# ADC_PLL.net
KiCad netlist of a schematic drawn in Altium Designer
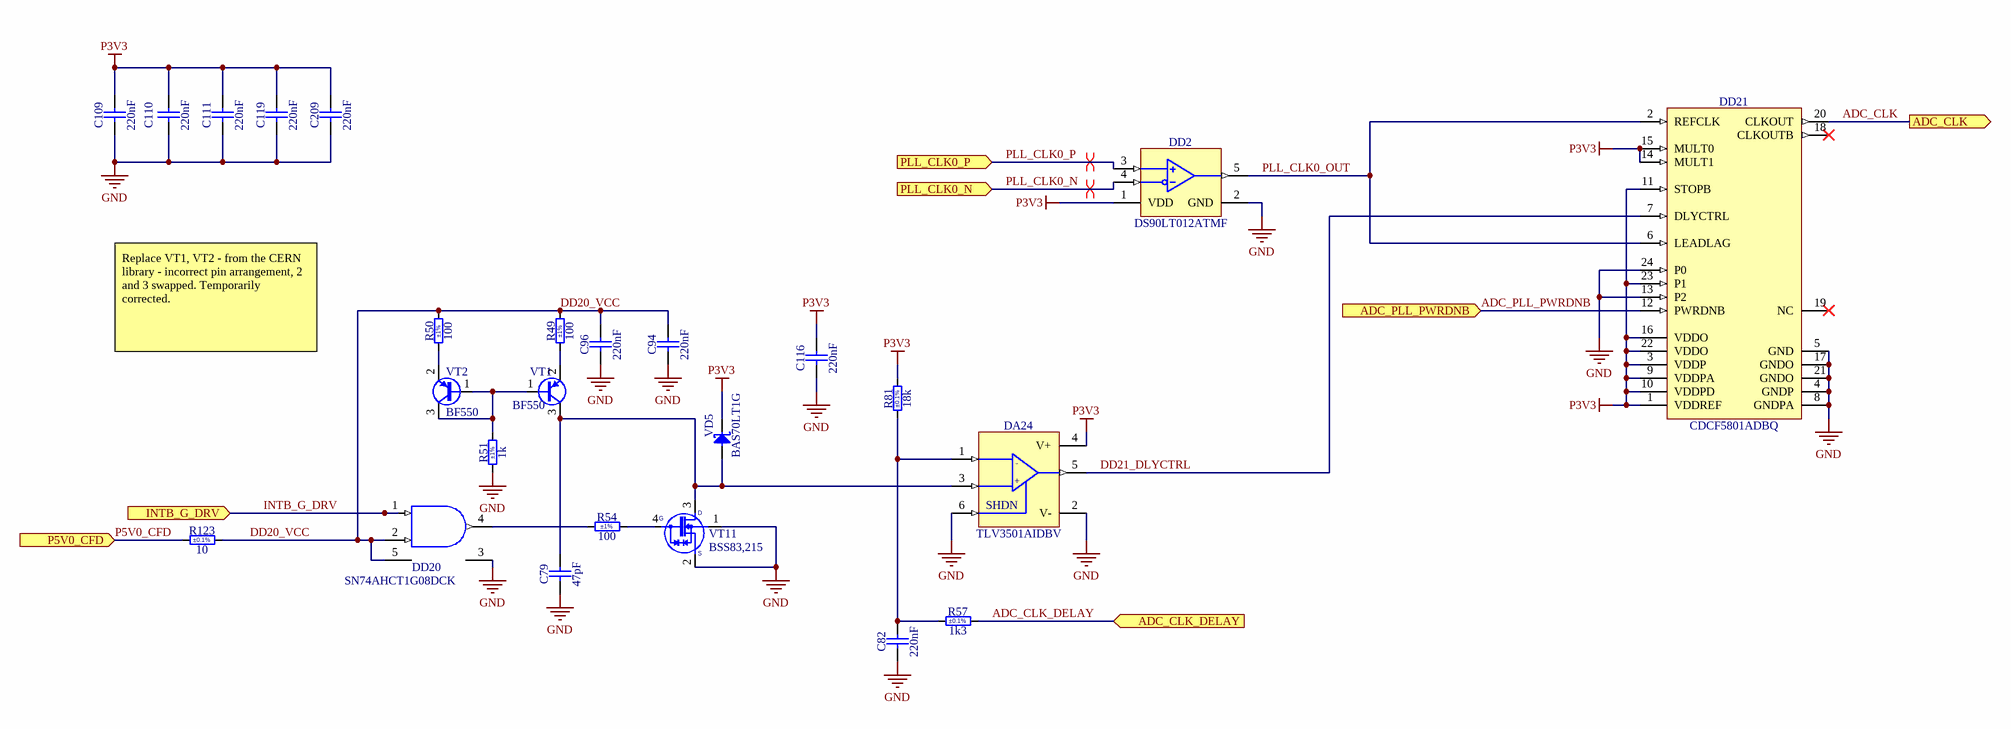
[diagram p0: ADC_PLL.SchDoc]

(export (version "E")
  (design (tool "Eeschema 10.0.6"))
  (components
    (comp (ref "C79")
      (value "47pF")
      (footprint "CAPC2012X140N")
      (description "Non-polarised capacitor")
      (fields
        (field (name "PART NUMBER") "CC0805_47pF_50V_2%_X8R")
        (field (name "VOLTAGE") "50V")
        (field (name "AUTHOR") "CERN DEM HF")
      )
      (libsource (lib "Capacitors") (part "Capacitor - non polarized"))
    )
    (comp (ref "C82")
      (value "220nF")
      (footprint "CAPC2012X135N")
      (description "Non-polarised capacitor")
      (fields
        (field (name "PART NUMBER") "CC0805_220NF_50V_10%_X7R")
        (field (name "VOLTAGE") "50V")
        (field (name "AUTHOR") "CERN DEM JLC")
      )
      (libsource (lib "Capacitors") (part "Capacitor - non polarized"))
    )
    (comp (ref "C94")
      (value "220nF")
      (footprint "CAPC2012X135N")
      (description "Non-polarised capacitor")
      (fields
        (field (name "PART NUMBER") "CC0805_220NF_50V_10%_X7R")
        (field (name "VOLTAGE") "50V")
        (field (name "AUTHOR") "CERN DEM JLC")
      )
      (libsource (lib "Capacitors") (part "Capacitor - non polarized"))
    )
    (comp (ref "C96")
      (value "220nF")
      (footprint "CAPC2012X135N")
      (description "Non-polarised capacitor")
      (fields
        (field (name "PART NUMBER") "CC0805_220NF_50V_10%_X7R")
        (field (name "VOLTAGE") "50V")
        (field (name "AUTHOR") "CERN DEM JLC")
      )
      (libsource (lib "Capacitors") (part "Capacitor - non polarized"))
    )
    (comp (ref "C109")
      (value "220nF")
      (footprint "CAPC2012X135N")
      (description "Non-polarised capacitor")
      (fields
        (field (name "PART NUMBER") "CC0805_220NF_50V_10%_X7R")
        (field (name "VOLTAGE") "50V")
        (field (name "AUTHOR") "CERN DEM JLC")
      )
      (libsource (lib "Capacitors") (part "Capacitor - non polarized"))
    )
    (comp (ref "C110")
      (value "220nF")
      (footprint "CAPC2012X135N")
      (description "Non-polarised capacitor")
      (fields
        (field (name "PART NUMBER") "CC0805_220NF_50V_10%_X7R")
        (field (name "VOLTAGE") "50V")
        (field (name "AUTHOR") "CERN DEM JLC")
      )
      (libsource (lib "Capacitors") (part "Capacitor - non polarized"))
    )
    (comp (ref "C111")
      (value "220nF")
      (footprint "CAPC2012X135N")
      (description "Non-polarised capacitor")
      (fields
        (field (name "PART NUMBER") "CC0805_220NF_50V_10%_X7R")
        (field (name "VOLTAGE") "50V")
        (field (name "AUTHOR") "CERN DEM JLC")
      )
      (libsource (lib "Capacitors") (part "Capacitor - non polarized"))
    )
    (comp (ref "C116")
      (value "220nF")
      (footprint "CAPC2012X135N")
      (description "Non-polarised capacitor")
      (fields
        (field (name "PART NUMBER") "CC0805_220NF_50V_10%_X7R")
        (field (name "VOLTAGE") "50V")
        (field (name "AUTHOR") "CERN DEM JLC")
      )
      (libsource (lib "Capacitors") (part "Capacitor - non polarized"))
    )
    (comp (ref "C119")
      (value "220nF")
      (footprint "CAPC2012X135N")
      (description "Non-polarised capacitor")
      (fields
        (field (name "PART NUMBER") "CC0805_220NF_50V_10%_X7R")
        (field (name "VOLTAGE") "50V")
        (field (name "AUTHOR") "CERN DEM JLC")
      )
      (libsource (lib "Capacitors") (part "Capacitor - non polarized"))
    )
    (comp (ref "C209")
      (value "220nF")
      (footprint "CAPC2012X135N")
      (description "Non-polarised capacitor")
      (fields
        (field (name "PART NUMBER") "CC0805_220NF_50V_10%_X7R")
        (field (name "VOLTAGE") "50V")
        (field (name "AUTHOR") "CERN DEM JLC")
      )
      (libsource (lib "Capacitors") (part "Capacitor - non polarized"))
    )
    (comp (ref "DA24")
      (value "TLV3501AIDBV")
      (footprint "SOT95P280X145-6N")
      (description "Wideband, Fixed Gain, Video Buffer Amplifier With Disable")
      (fields (field (name "MANUFACTURER") "TEXAS INSTRUMENTS") (field (name "AUTHOR") "CERN DEM HF"))
      (libsource (lib "ICs And Semiconductors") (part "TLV3501AIDBV"))
    )
    (comp (ref "DD2")
      (value "DS90LT012ATMF")
      (footprint "SOT95P280X145-5N")
      (description "3V LVDS Single CMOS Differential Line Receiver")
      (fields (field (name "MANUFACTURER") "TEXAS INSTRUMENTS") (field (name "AUTHOR") "CERN DEM HF"))
      (libsource (lib "ICs And Semiconductors") (part "DS90LT012A"))
    )
    (comp (ref "DD20")
      (value "SN74AHCT1G08DCK")
      (footprint "SOT65P210X110-5N")
      (description "Single 2-Input AND Gate")
      (fields (field (name "MANUFACTURER") "TEXAS INSTRUMENTS") (field (name "AUTHOR") "CERN DEM HF"))
      (libsource (lib "ICs And Semiconductors") (part "741G08"))
    )
    (comp (ref "DD21")
      (value "CDCF5801ADBQ")
      (footprint "SOP63P600X175-24N")
      (description "Clock Multiplier with Delay Control and Phase Alignment")
      (fields (field (name "MANUFACTURER") "TEXAS INSTRUMENTS") (field (name "AUTHOR") "CERN DEM HF"))
      (libsource (lib "ICs And Semiconductors") (part "CDCF5801ADBQ"))
    )
    (comp (ref "R49")
      (value "100")
      (footprint "RESC2012X60N")
      (description "Resistor - 1%")
      (fields
        (field (name "TOLERANCE") "±1%")
        (field (name "PART NUMBER") "R0805_100R_1%_0.125W_100PPM")
        (field (name "POWER") "0.125W")
        (field (name "AUTHOR") "CERN DEM JLC")
      )
      (libsource (lib "Resistors") (part "Resistor - 1%"))
    )
    (comp (ref "R50")
      (value "100")
      (footprint "RESC2012X60N")
      (description "Resistor - 1%")
      (fields
        (field (name "TOLERANCE") "±1%")
        (field (name "PART NUMBER") "R0805_100R_1%_0.125W_100PPM")
        (field (name "POWER") "0.125W")
        (field (name "AUTHOR") "CERN DEM JLC")
      )
      (libsource (lib "Resistors") (part "Resistor - 1%"))
    )
    (comp (ref "R51")
      (value "1k")
      (footprint "RESC2012X60N")
      (description "Resistor - 1%")
      (fields
        (field (name "TOLERANCE") "±1%")
        (field (name "PART NUMBER") "R0805_1K_1%_0.125W_100PPM")
        (field (name "POWER") "0.125W")
        (field (name "AUTHOR") "CERN DEM JLC")
      )
      (libsource (lib "Resistors") (part "Resistor - 1%"))
    )
    (comp (ref "R54")
      (value "100")
      (footprint "RESC1608X55N")
      (description "Resistor - 1%")
      (fields
        (field (name "TOLERANCE") "±1%")
        (field (name "PART NUMBER") "R0603_100R_1%_0.1W_100PPM")
        (field (name "POWER") "0.1W")
        (field (name "AUTHOR") "CERN DEM JLC")
      )
      (libsource (lib "Resistors") (part "Resistor - 1%"))
    )
    (comp (ref "R57")
      (value "1k3")
      (footprint "RESC2012X60N")
      (description "Resistor - 0.1%")
      (fields
        (field (name "TOLERANCE") "±0.1%")
        (field (name "PART NUMBER") "R0805_1K3_0.1%_0.1W_10PPM")
        (field (name "POWER") "0.1W")
        (field (name "AUTHOR") "CERN DEM JLC")
      )
      (libsource (lib "Resistors") (part "Resistor - 0.1%"))
    )
    (comp (ref "R81")
      (value "18k")
      (footprint "RESC2012X60N")
      (description "Resistor - 0.1%")
      (fields
        (field (name "TOLERANCE") "±0.1%")
        (field (name "PART NUMBER") "R0805_18K_0.1%_0.125W_10PPM")
        (field (name "POWER") "0.125W")
        (field (name "AUTHOR") "CERN DEM HF")
      )
      (libsource (lib "Resistors") (part "Resistor - 0.1%"))
    )
    (comp (ref "R123")
      (value "10")
      (footprint "RESC2012X60N")
      (description "Resistor - 0.1%")
      (fields
        (field (name "TOLERANCE") "±0.1%")
        (field (name "PART NUMBER") "R0805_10R_0.1%_0.1W_10PPM")
        (field (name "POWER") "0.1W")
        (field (name "AUTHOR") "CERN DEM JLC")
      )
      (libsource (lib "Resistors") (part "Resistor - 0.1%"))
    )
    (comp (ref "VD5")
      (value "BAS70LT1G")
      (footprint "SOT95P240X110-3N")
      (description "Diode Schottky  Anode Pin 1 Cathode Pin 3 (Pas de pin 2)")
      (fields
        (field (name "VOLTAGE") "70V")
        (field (name "POWER") "70mA")
        (field (name "AUTHOR") "CERN DEM JLC")
      )
      (libsource (lib "ICs And Semiconductors") (part "Diode Schottky A1C3"))
    )
    (comp (ref "VT1")
      (value "BF550")
      (footprint "SOT95P230X110-3N")
      (description "PNP Transistor")
      (fields (field (name "MANUFACTURER") "NXP SEMICONDUCTORS") (field (name "AUTHOR") "CERN DEM HF"))
      (libsource (lib "ICs And Semiconductors") (part "PNP B1 C2 E3"))
    )
    (comp (ref "VT2")
      (value "BF550")
      (footprint "SOT95P230X110-3N")
      (description "PNP Transistor")
      (fields (field (name "MANUFACTURER") "NXP SEMICONDUCTORS") (field (name "AUTHOR") "CERN DEM HF"))
      (libsource (lib "ICs And Semiconductors") (part "PNP B1 C2 E3"))
    )
    (comp (ref "VT11")
      (value "BSS83,215")
      (footprint "SOT143N")
      (description "10V, 50 mA N-Channel Enhancement Switching Transistor")
      (fields (field (name "MANUFACTURER") "NXP SEMICONDUCTORS") (field (name "AUTHOR") "CERN DEM JLC"))
      (libsource (lib "ICs And Semiconductors") (part "BSS83"))
    )
  )
  (nets
    (net (code "1") (name "/ADC_CLK") (class "Default")
      (node (ref "DD21") (pin "20") (pinfunction "CLKOUT_20") (pintype "output"))
    )
    (net (code "2") (name "/ADC_CLK_DELAY") (class "Default")
      (node (ref "R57") (pin "2") (pinfunction "2_2") (pintype "passive"))
    )
    (net (code "3") (name "/ADC_PLL_PWRDNB") (class "Default")
      (node (ref "DD21") (pin "12") (pinfunction "PWRDNB_12") (pintype "input"))
    )
    (net (code "4") (name "/DD20_VCC") (class "Default")
      (node (ref "C94") (pin "2") (pinfunction "2_2") (pintype "passive"))
      (node (ref "C96") (pin "2") (pinfunction "2_2") (pintype "passive"))
      (node (ref "DD20") (pin "2") (pinfunction "A_2") (pintype "input"))
      (node (ref "DD20") (pin "5") (pinfunction "VCC_5") (pintype "power_in"))
      (node (ref "R123") (pin "2") (pinfunction "2_2") (pintype "passive"))
      (node (ref "R49") (pin "2") (pinfunction "2_2") (pintype "passive"))
      (node (ref "R50") (pin "2") (pinfunction "2_2") (pintype "passive"))
    )
    (net (code "5") (name "/DD21_DLYCTRL") (class "Default")
      (node (ref "DA24") (pin "5") (pinfunction "OUT_5") (pintype "output"))
      (node (ref "DD21") (pin "7") (pinfunction "DLYCTRL_7") (pintype "input"))
    )
    (net (code "6") (name "/INTB_G_DRV") (class "Default")
      (node (ref "DD20") (pin "1") (pinfunction "B_1") (pintype "input"))
    )
    (net (code "7") (name "/P5V0_CFD") (class "Default")
      (node (ref "R123") (pin "1") (pinfunction "1_1") (pintype "passive"))
    )
    (net (code "8") (name "/PLL_CLK0_N") (class "Default")
      (node (ref "DD2") (pin "4") (pinfunction "IN-_4") (pintype "input"))
    )
    (net (code "9") (name "/PLL_CLK0_OUT") (class "Default")
      (node (ref "DD2") (pin "5") (pinfunction "TTLOUT_5") (pintype "output"))
      (node (ref "DD21") (pin "2") (pinfunction "REFCLK_2") (pintype "input"))
      (node (ref "DD21") (pin "6") (pinfunction "LEADLAG_6") (pintype "input"))
    )
    (net (code "10") (name "/PLL_CLK0_P") (class "Default")
      (node (ref "DD2") (pin "3") (pinfunction "IN+_3") (pintype "input"))
    )
    (net (code "11") (name "GND") (class "Default")
      (node (ref "C109") (pin "1") (pinfunction "1_1") (pintype "passive"))
      (node (ref "C110") (pin "1") (pinfunction "1_1") (pintype "passive"))
      (node (ref "C111") (pin "1") (pinfunction "1_1") (pintype "passive"))
      (node (ref "C116") (pin "1") (pinfunction "1_1") (pintype "passive"))
      (node (ref "C119") (pin "1") (pinfunction "1_1") (pintype "passive"))
      (node (ref "C209") (pin "1") (pinfunction "1_1") (pintype "passive"))
      (node (ref "C79") (pin "1") (pinfunction "1_1") (pintype "passive"))
      (node (ref "C82") (pin "1") (pinfunction "1_1") (pintype "passive"))
      (node (ref "C94") (pin "1") (pinfunction "1_1") (pintype "passive"))
      (node (ref "C96") (pin "1") (pinfunction "1_1") (pintype "passive"))
      (node (ref "DA24") (pin "2") (pinfunction "V-_2") (pintype "power_in"))
      (node (ref "DA24") (pin "6") (pinfunction "SHDN_6") (pintype "input"))
      (node (ref "DD2") (pin "2") (pinfunction "GND_2") (pintype "power_in"))
      (node (ref "DD20") (pin "3") (pinfunction "GND_3") (pintype "power_in"))
      (node (ref "DD21") (pin "13") (pinfunction "P2_13") (pintype "input"))
      (node (ref "DD21") (pin "17") (pinfunction "GNDO_17") (pintype "power_in"))
      (node (ref "DD21") (pin "21") (pinfunction "GNDO_21") (pintype "power_in"))
      (node (ref "DD21") (pin "24") (pinfunction "P0_24") (pintype "input"))
      (node (ref "DD21") (pin "4") (pinfunction "GNDP_4") (pintype "power_in"))
      (node (ref "DD21") (pin "5") (pinfunction "GND_5") (pintype "power_in"))
      (node (ref "DD21") (pin "8") (pinfunction "GNDPA_8") (pintype "power_in"))
      (node (ref "R51") (pin "1") (pinfunction "1_1") (pintype "passive"))
      (node (ref "VT11") (pin "1") (pinfunction "SUB_1") (pintype "passive"))
      (node (ref "VT11") (pin "2") (pinfunction "S_2") (pintype "passive"))
    )
    (net (code "12") (name "Net-(DA24-+IN)") (class "Default")
      (node (ref "C79") (pin "2") (pinfunction "2_2") (pintype "passive"))
      (node (ref "DA24") (pin "3") (pinfunction "+IN_3") (pintype "input"))
      (node (ref "VD5") (pin "1") (pinfunction "A_1") (pintype "passive"))
      (node (ref "VT1") (pin "3") (pinfunction "E_3") (pintype "passive"))
      (node (ref "VT11") (pin "3") (pinfunction "D_3") (pintype "passive"))
    )
    (net (code "13") (name "Net-(DA24--IN)") (class "Default")
      (node (ref "C82") (pin "2") (pinfunction "2_2") (pintype "passive"))
      (node (ref "DA24") (pin "1") (pinfunction "-IN_1") (pintype "input"))
      (node (ref "R57") (pin "1") (pinfunction "1_1") (pintype "passive"))
      (node (ref "R81") (pin "1") (pinfunction "1_1") (pintype "passive"))
    )
    (net (code "14") (name "Net-(DD20-Y)") (class "Default")
      (node (ref "DD20") (pin "4") (pinfunction "Y_4") (pintype "output"))
      (node (ref "R54") (pin "1") (pinfunction "1_1") (pintype "passive"))
    )
    (net (code "15") (name "Net-(VT1-B)") (class "Default")
      (node (ref "R51") (pin "2") (pinfunction "2_2") (pintype "passive"))
      (node (ref "VT1") (pin "1") (pinfunction "B_1") (pintype "passive"))
      (node (ref "VT2") (pin "1") (pinfunction "B_1") (pintype "passive"))
      (node (ref "VT2") (pin "3") (pinfunction "E_3") (pintype "passive"))
    )
    (net (code "16") (name "Net-(VT1-C)") (class "Default")
      (node (ref "R49") (pin "1") (pinfunction "1_1") (pintype "passive"))
      (node (ref "VT1") (pin "2") (pinfunction "C_2") (pintype "passive"))
    )
    (net (code "17") (name "Net-(VT2-C)") (class "Default")
      (node (ref "R50") (pin "1") (pinfunction "1_1") (pintype "passive"))
      (node (ref "VT2") (pin "2") (pinfunction "C_2") (pintype "passive"))
    )
    (net (code "18") (name "Net-(VT11-G)") (class "Default")
      (node (ref "R54") (pin "2") (pinfunction "2_2") (pintype "passive"))
      (node (ref "VT11") (pin "4") (pinfunction "G_4") (pintype "passive"))
    )
    (net (code "19") (name "P3V3") (class "Default")
      (node (ref "C109") (pin "2") (pinfunction "2_2") (pintype "passive"))
      (node (ref "C110") (pin "2") (pinfunction "2_2") (pintype "passive"))
      (node (ref "C111") (pin "2") (pinfunction "2_2") (pintype "passive"))
      (node (ref "C116") (pin "2") (pinfunction "2_2") (pintype "passive"))
      (node (ref "C119") (pin "2") (pinfunction "2_2") (pintype "passive"))
      (node (ref "C209") (pin "2") (pinfunction "2_2") (pintype "passive"))
      (node (ref "DA24") (pin "4") (pinfunction "V+_4") (pintype "power_in"))
      (node (ref "DD2") (pin "1") (pinfunction "VDD_1") (pintype "power_in"))
      (node (ref "DD21") (pin "1") (pinfunction "VDDREF_1") (pintype "power_in"))
      (node (ref "DD21") (pin "10") (pinfunction "VDDPD_10") (pintype "power_in"))
      (node (ref "DD21") (pin "11") (pinfunction "STOPB_11") (pintype "input"))
      (node (ref "DD21") (pin "14") (pinfunction "MULT1_14") (pintype "input"))
      (node (ref "DD21") (pin "15") (pinfunction "MULT0_15") (pintype "input"))
      (node (ref "DD21") (pin "16") (pinfunction "VDDO_16") (pintype "power_in"))
      (node (ref "DD21") (pin "22") (pinfunction "VDDO_22") (pintype "power_in"))
      (node (ref "DD21") (pin "23") (pinfunction "P1_23") (pintype "input"))
      (node (ref "DD21") (pin "3") (pinfunction "VDDP_3") (pintype "power_in"))
      (node (ref "DD21") (pin "9") (pinfunction "VDDPA_9") (pintype "power_in"))
      (node (ref "R81") (pin "2") (pinfunction "2_2") (pintype "passive"))
      (node (ref "VD5") (pin "3") (pinfunction "C_3") (pintype "passive"))
    )
    (net (code "20") (name "unconnected-(DD21-CLKOUTB-Pad18)") (class "Default")
      (node (ref "DD21") (pin "18") (pinfunction "CLKOUTB_18") (pintype "output+no_connect"))
    )
    (net (code "21") (name "unconnected-(DD21-NC-Pad19)") (class "Default")
      (node (ref "DD21") (pin "19") (pinfunction "NC_19") (pintype "passive+no_connect"))
    )
  )
)
